# diferenciator.net
KiCad netlist of a schematic drawn in Altium Designer
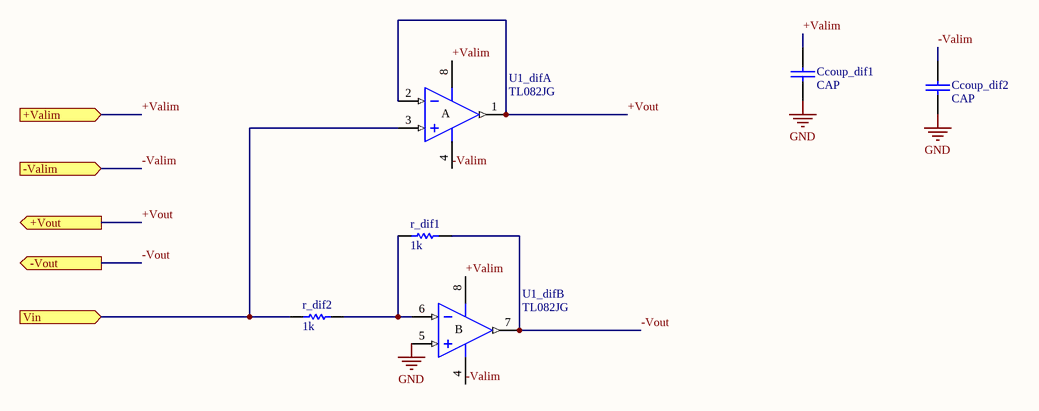
[diagram p0: diferenciator.SchDoc]

(export (version "E")
  (design (tool "Eeschema 10.0.6"))
  (components
    (comp (ref "Ccoup_dif1") (value "CAP") (footprint "CAP200") (libsource (lib "LIBEBAL") (part "CAP")))
    (comp (ref "Ccoup_dif2") (value "CAP") (footprint "CAP200") (libsource (lib "LIBEBAL") (part "CAP")))
    (comp (ref "r_dif1") (value "1k") (footprint "RES300") (libsource (lib "LIBEBAL") (part "RES")))
    (comp (ref "r_dif2") (value "1k") (footprint "RES300") (libsource (lib "LIBEBAL") (part "RES")))
    (comp (ref "U1_dif")
      (value "TL082JG")
      (footprint "JG008")
      (description "JFET-Input Operational Amplifier")
      (fields (field (name "PUBLISHER") "Altium Limited"))
      (libsource (lib "TI Operational Amplifier") (part "TL082JG"))
    )
  )
  (nets
    (net (code "1") (name "/+Valim") (class "Default")
      (node (ref "Ccoup_dif1") (pin "1") (pinfunction "1_1") (pintype "passive"))
      (node (ref "U1_dif") (pin "8") (pinfunction "V+_8") (pintype "power_in"))
    )
    (net (code "2") (name "/+Vout") (class "Default")
      (node (ref "U1_dif") (pin "1") (pinfunction "OUT_1") (pintype "output"))
      (node (ref "U1_dif") (pin "2") (pinfunction "IN-_2") (pintype "input"))
    )
    (net (code "3") (name "/-Valim") (class "Default")
      (node (ref "Ccoup_dif2") (pin "1") (pinfunction "1_1") (pintype "passive"))
      (node (ref "U1_dif") (pin "4") (pinfunction "V-_4") (pintype "power_in"))
    )
    (net (code "4") (name "/-Vout") (class "Default")
      (node (ref "U1_dif") (pin "7") (pinfunction "OUT_7") (pintype "output"))
      (node (ref "r_dif1") (pin "2") (pinfunction "2_2") (pintype "passive"))
    )
    (net (code "5") (name "/Vin") (class "Default")
      (node (ref "U1_dif") (pin "3") (pinfunction "IN+_3") (pintype "input"))
      (node (ref "r_dif2") (pin "1") (pinfunction "1_1") (pintype "passive"))
    )
    (net (code "6") (name "GND") (class "Default")
      (node (ref "Ccoup_dif1") (pin "2") (pinfunction "2_2") (pintype "passive"))
      (node (ref "Ccoup_dif2") (pin "2") (pinfunction "2_2") (pintype "passive"))
      (node (ref "U1_dif") (pin "5") (pinfunction "IN+_5") (pintype "input"))
    )
    (net (code "7") (name "Net-(U1_difB-IN-)") (class "Default")
      (node (ref "U1_dif") (pin "6") (pinfunction "IN-_6") (pintype "input"))
      (node (ref "r_dif1") (pin "1") (pinfunction "1_1") (pintype "passive"))
      (node (ref "r_dif2") (pin "2") (pinfunction "2_2") (pintype "passive"))
    )
  )
)
